# HelveTiny85_3_3V.net
KiCad netlist of a schematic drawn in EAGLE
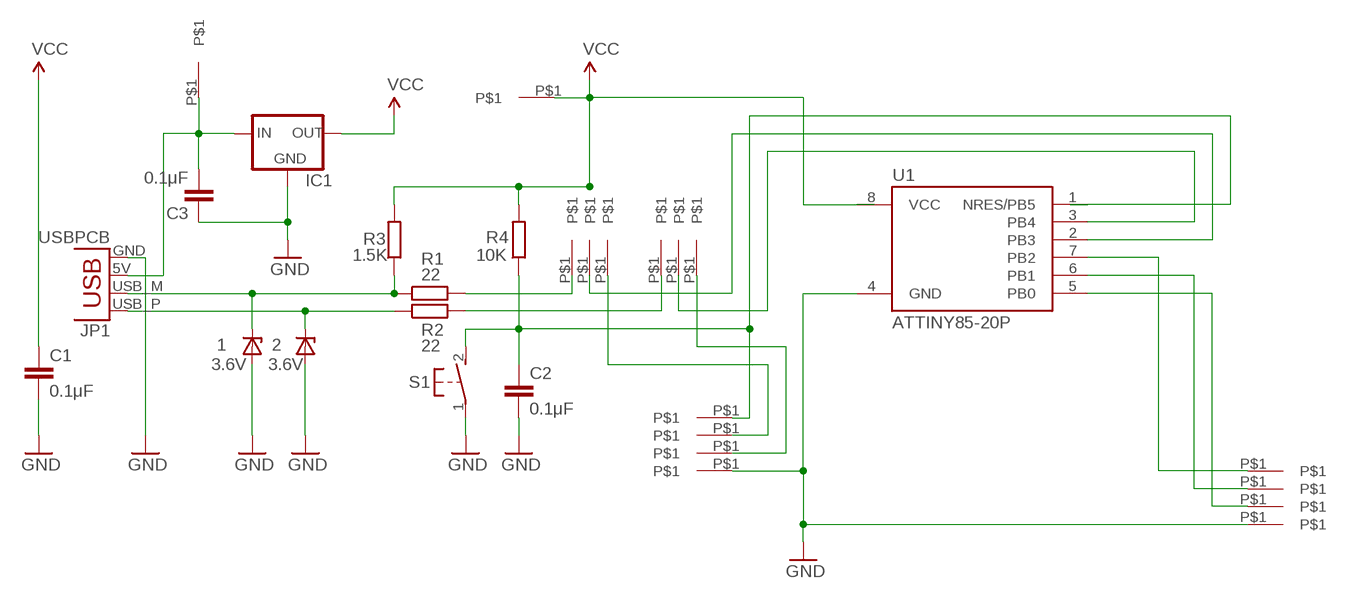
[diagram p0: schematic, sheet 1]

(export (version "E")
  (design (tool "Eeschema 10.0.6"))
  (components
    (comp (ref "1")
      (value "3.6V")
      (footprint "eagle-import:ZDIO-7.5")
      (libsource (lib "eagle-import") (part "ZENER-DIODEZD-7.5"))
    )
    (comp (ref "2")
      (value "3.6V")
      (footprint "eagle-import:ZDIO-7.5")
      (libsource (lib "eagle-import") (part "ZENER-DIODEZD-7.5"))
    )
    (comp (ref "C1")
      (value "0.1μF")
      (footprint "eagle-import:C025-024X044")
      (libsource (lib "eagle-import") (part "C-EU025-024X044"))
    )
    (comp (ref "C2")
      (value "0.1μF")
      (footprint "eagle-import:C025-024X044")
      (libsource (lib "eagle-import") (part "C-EU025-024X044"))
    )
    (comp (ref "C3")
      (value "0.1μF")
      (footprint "eagle-import:C025-024X044")
      (libsource (lib "eagle-import") (part "C-EU025-024X044"))
    )
    (comp (ref "IC1")
      (value "MCP1700TRI")
      (footprint "eagle-import:TO92")
      (libsource (lib "eagle-import") (part "MCP1700TRI"))
    )
    (comp (ref "JP1")
      (value "USBPCB")
      (footprint "eagle-import:USB-A-PCB")
      (libsource (lib "eagle-import") (part "USBPCB"))
    )
    (comp (ref "R1")
      (value "22")
      (footprint "eagle-import:0207_7")
      (libsource (lib "eagle-import") (part "R-EU_0207/7"))
    )
    (comp (ref "R2")
      (value "22")
      (footprint "eagle-import:0207_7")
      (libsource (lib "eagle-import") (part "R-EU_0207/7"))
    )
    (comp (ref "R3")
      (value "1.5K")
      (footprint "eagle-import:0207_7")
      (libsource (lib "eagle-import") (part "R-EU_0207/7"))
    )
    (comp (ref "R4")
      (value "10K")
      (footprint "eagle-import:0207_7")
      (libsource (lib "eagle-import") (part "R-EU_0207/7"))
    )
    (comp (ref "S1")
      (value "S3")
      (footprint "eagle-import:DTS-3")
      (libsource (lib "eagle-import") (part "DTS-3"))
    )
    (comp (ref "TP1")
      (value "FLOWERPIN")
      (footprint "eagle-import:FLOWERPIN")
      (libsource (lib "eagle-import") (part "FLOWERPIN"))
    )
    (comp (ref "TP2")
      (value "FLOWERPIN")
      (footprint "eagle-import:FLOWERPIN")
      (libsource (lib "eagle-import") (part "FLOWERPIN"))
    )
    (comp (ref "TP3")
      (value "FLOWERPIN")
      (footprint "eagle-import:FLOWERPIN")
      (libsource (lib "eagle-import") (part "FLOWERPIN"))
    )
    (comp (ref "TP4")
      (value "FLOWERPIN")
      (footprint "eagle-import:FLOWERPIN")
      (libsource (lib "eagle-import") (part "FLOWERPIN"))
    )
    (comp (ref "TP5")
      (value "FLOWERPIN")
      (footprint "eagle-import:FLOWERPIN")
      (libsource (lib "eagle-import") (part "FLOWERPIN"))
    )
    (comp (ref "TP6")
      (value "FLOWERPIN")
      (footprint "eagle-import:FLOWERPIN")
      (libsource (lib "eagle-import") (part "FLOWERPIN"))
    )
    (comp (ref "TP7")
      (value "FLOWERPIN")
      (footprint "eagle-import:FLOWERPIN")
      (libsource (lib "eagle-import") (part "FLOWERPIN"))
    )
    (comp (ref "TP8")
      (value "FLOWERPIN")
      (footprint "eagle-import:FLOWERPIN")
      (fields (field (name "SPICEPREFIX") "X"))
      (libsource (lib "eagle-import") (part "FLOWERPIN"))
    )
    (comp (ref "TP29")
      (value "FLOWERPIN")
      (footprint "eagle-import:FLOWERPIN")
      (libsource (lib "eagle-import") (part "FLOWERPIN"))
    )
    (comp (ref "TP30")
      (value "FLOWERPIN")
      (footprint "eagle-import:FLOWERPIN")
      (libsource (lib "eagle-import") (part "FLOWERPIN"))
    )
    (comp (ref "TP31")
      (value "FLOWERPIN")
      (footprint "eagle-import:FLOWERPIN")
      (libsource (lib "eagle-import") (part "FLOWERPIN"))
    )
    (comp (ref "TP32")
      (value "FLOWERPIN")
      (footprint "eagle-import:FLOWERPIN")
      (libsource (lib "eagle-import") (part "FLOWERPIN"))
    )
    (comp (ref "TP33")
      (value "FLOWERPIN")
      (footprint "eagle-import:FLOWERPIN")
      (libsource (lib "eagle-import") (part "FLOWERPIN"))
    )
    (comp (ref "TP34")
      (value "FLOWERPIN")
      (footprint "eagle-import:FLOWERPIN")
      (libsource (lib "eagle-import") (part "FLOWERPIN"))
    )
    (comp (ref "TP35")
      (value "FLOWERPIN")
      (footprint "eagle-import:FLOWERPIN")
      (libsource (lib "eagle-import") (part "FLOWERPIN"))
    )
    (comp (ref "TP36")
      (value "FLOWERPIN")
      (footprint "eagle-import:FLOWERPIN")
      (libsource (lib "eagle-import") (part "FLOWERPIN"))
    )
    (comp (ref "U1")
      (value "ATTINY85-20P")
      (footprint "eagle-import:PDIP08_300MIL")
      (libsource (lib "eagle-import") (part "ATTINY85P-20"))
    )
  )
  (nets
    (net (code "1") (name "GND") (class "Default")
      (node (ref "1") (pin "A") (pinfunction "A_A") (pintype "passive"))
      (node (ref "2") (pin "A") (pinfunction "A_A") (pintype "passive"))
      (node (ref "C1") (pin "2") (pinfunction "2_2") (pintype "passive"))
      (node (ref "C2") (pin "2") (pinfunction "2_2") (pintype "passive"))
      (node (ref "C3") (pin "1") (pinfunction "1_1") (pintype "passive"))
      (node (ref "IC1") (pin "1") (pinfunction "GND_1") (pintype "input"))
      (node (ref "JP1") (pin "GND") (pinfunction "GND_GND") (pintype "bidirectional"))
      (node (ref "S1") (pin "1") (pinfunction "1_1") (pintype "passive"))
      (node (ref "TP32") (pin "P$1") (pinfunction "P$1_P$1") (pintype "bidirectional"))
      (node (ref "TP7") (pin "P$1") (pinfunction "P$1_P$1") (pintype "bidirectional"))
      (node (ref "U1") (pin "4") (pinfunction "GND_4") (pintype "power_in"))
    )
    (net (code "2") (name "Net-(IC1-IN)") (class "Default")
      (node (ref "C3") (pin "2") (pinfunction "2_2") (pintype "passive"))
      (node (ref "IC1") (pin "2") (pinfunction "IN_2") (pintype "input"))
      (node (ref "JP1") (pin "5V") (pinfunction "VBUS_5V") (pintype "bidirectional"))
      (node (ref "TP8") (pin "P$1") (pinfunction "P$1_P$1") (pintype "bidirectional"))
    )
    (net (code "3") (name "Net-(JP1-D+)") (class "Default")
      (node (ref "2") (pin "C") (pinfunction "C_C") (pintype "passive"))
      (node (ref "JP1") (pin "USB_P") (pinfunction "D+_USB_P") (pintype "bidirectional"))
      (node (ref "R2") (pin "1") (pinfunction "1_1") (pintype "passive"))
    )
    (net (code "4") (name "Net-(JP1-D-)") (class "Default")
      (node (ref "1") (pin "C") (pinfunction "C_C") (pintype "passive"))
      (node (ref "JP1") (pin "USB_M") (pinfunction "D-_USB_M") (pintype "bidirectional"))
      (node (ref "R1") (pin "1") (pinfunction "1_1") (pintype "passive"))
      (node (ref "R3") (pin "1") (pinfunction "1_1") (pintype "passive"))
    )
    (net (code "5") (name "Net-(R1-Pad2)") (class "Default")
      (node (ref "R1") (pin "2") (pinfunction "2_2") (pintype "passive"))
      (node (ref "TP2") (pin "P$1") (pinfunction "P$1_P$1") (pintype "bidirectional"))
    )
    (net (code "6") (name "Net-(R2-Pad2)") (class "Default")
      (node (ref "R2") (pin "2") (pinfunction "2_2") (pintype "passive"))
      (node (ref "TP4") (pin "P$1") (pinfunction "P$1_P$1") (pintype "bidirectional"))
    )
    (net (code "7") (name "Net-(TP1-PadP$1)") (class "Default")
      (node (ref "TP1") (pin "P$1") (pinfunction "P$1_P$1") (pintype "bidirectional"))
      (node (ref "TP3") (pin "P$1") (pinfunction "P$1_P$1") (pintype "bidirectional"))
    )
    (net (code "8") (name "Net-(TP31-PadP$1)") (class "Default")
      (node (ref "TP31") (pin "P$1") (pinfunction "P$1_P$1") (pintype "bidirectional"))
      (node (ref "TP6") (pin "P$1") (pinfunction "P$1_P$1") (pintype "bidirectional"))
    )
    (net (code "9") (name "Net-(U1-NRES{slash}PB5)") (class "Default")
      (node (ref "C2") (pin "1") (pinfunction "1_1") (pintype "passive"))
      (node (ref "R4") (pin "1") (pinfunction "1_1") (pintype "passive"))
      (node (ref "S1") (pin "2") (pinfunction "2_2") (pintype "passive"))
      (node (ref "TP29") (pin "P$1") (pinfunction "P$1_P$1") (pintype "bidirectional"))
      (node (ref "U1") (pin "1") (pinfunction "NRES/PB5_1") (pintype "bidirectional"))
    )
    (net (code "10") (name "Net-(U1-PB0)") (class "Default")
      (node (ref "TP35") (pin "P$1") (pinfunction "P$1_P$1") (pintype "bidirectional"))
      (node (ref "U1") (pin "5") (pinfunction "PB0_5") (pintype "bidirectional"))
    )
    (net (code "11") (name "Net-(U1-PB1)") (class "Default")
      (node (ref "TP34") (pin "P$1") (pinfunction "P$1_P$1") (pintype "bidirectional"))
      (node (ref "U1") (pin "6") (pinfunction "PB1_6") (pintype "bidirectional"))
    )
    (net (code "12") (name "Net-(U1-PB2)") (class "Default")
      (node (ref "TP33") (pin "P$1") (pinfunction "P$1_P$1") (pintype "bidirectional"))
      (node (ref "U1") (pin "7") (pinfunction "PB2_7") (pintype "bidirectional"))
    )
    (net (code "13") (name "Net-(U1-PB3)") (class "Default")
      (node (ref "TP30") (pin "P$1") (pinfunction "P$1_P$1") (pintype "bidirectional"))
      (node (ref "U1") (pin "2") (pinfunction "PB3_2") (pintype "bidirectional"))
    )
    (net (code "14") (name "Net-(U1-PB4)") (class "Default")
      (node (ref "TP5") (pin "P$1") (pinfunction "P$1_P$1") (pintype "bidirectional"))
      (node (ref "U1") (pin "3") (pinfunction "PB4_3") (pintype "bidirectional"))
    )
    (net (code "15") (name "VCC") (class "Default")
      (node (ref "C1") (pin "1") (pinfunction "1_1") (pintype "passive"))
      (node (ref "IC1") (pin "3") (pinfunction "OUT_3") (pintype "passive"))
      (node (ref "R3") (pin "2") (pinfunction "2_2") (pintype "passive"))
      (node (ref "R4") (pin "2") (pinfunction "2_2") (pintype "passive"))
      (node (ref "TP36") (pin "P$1") (pinfunction "P$1_P$1") (pintype "bidirectional"))
      (node (ref "U1") (pin "8") (pinfunction "VCC_8") (pintype "power_in"))
    )
  )
)
